# 14audio.net
KiCad netlist of a schematic drawn in Altium Designer
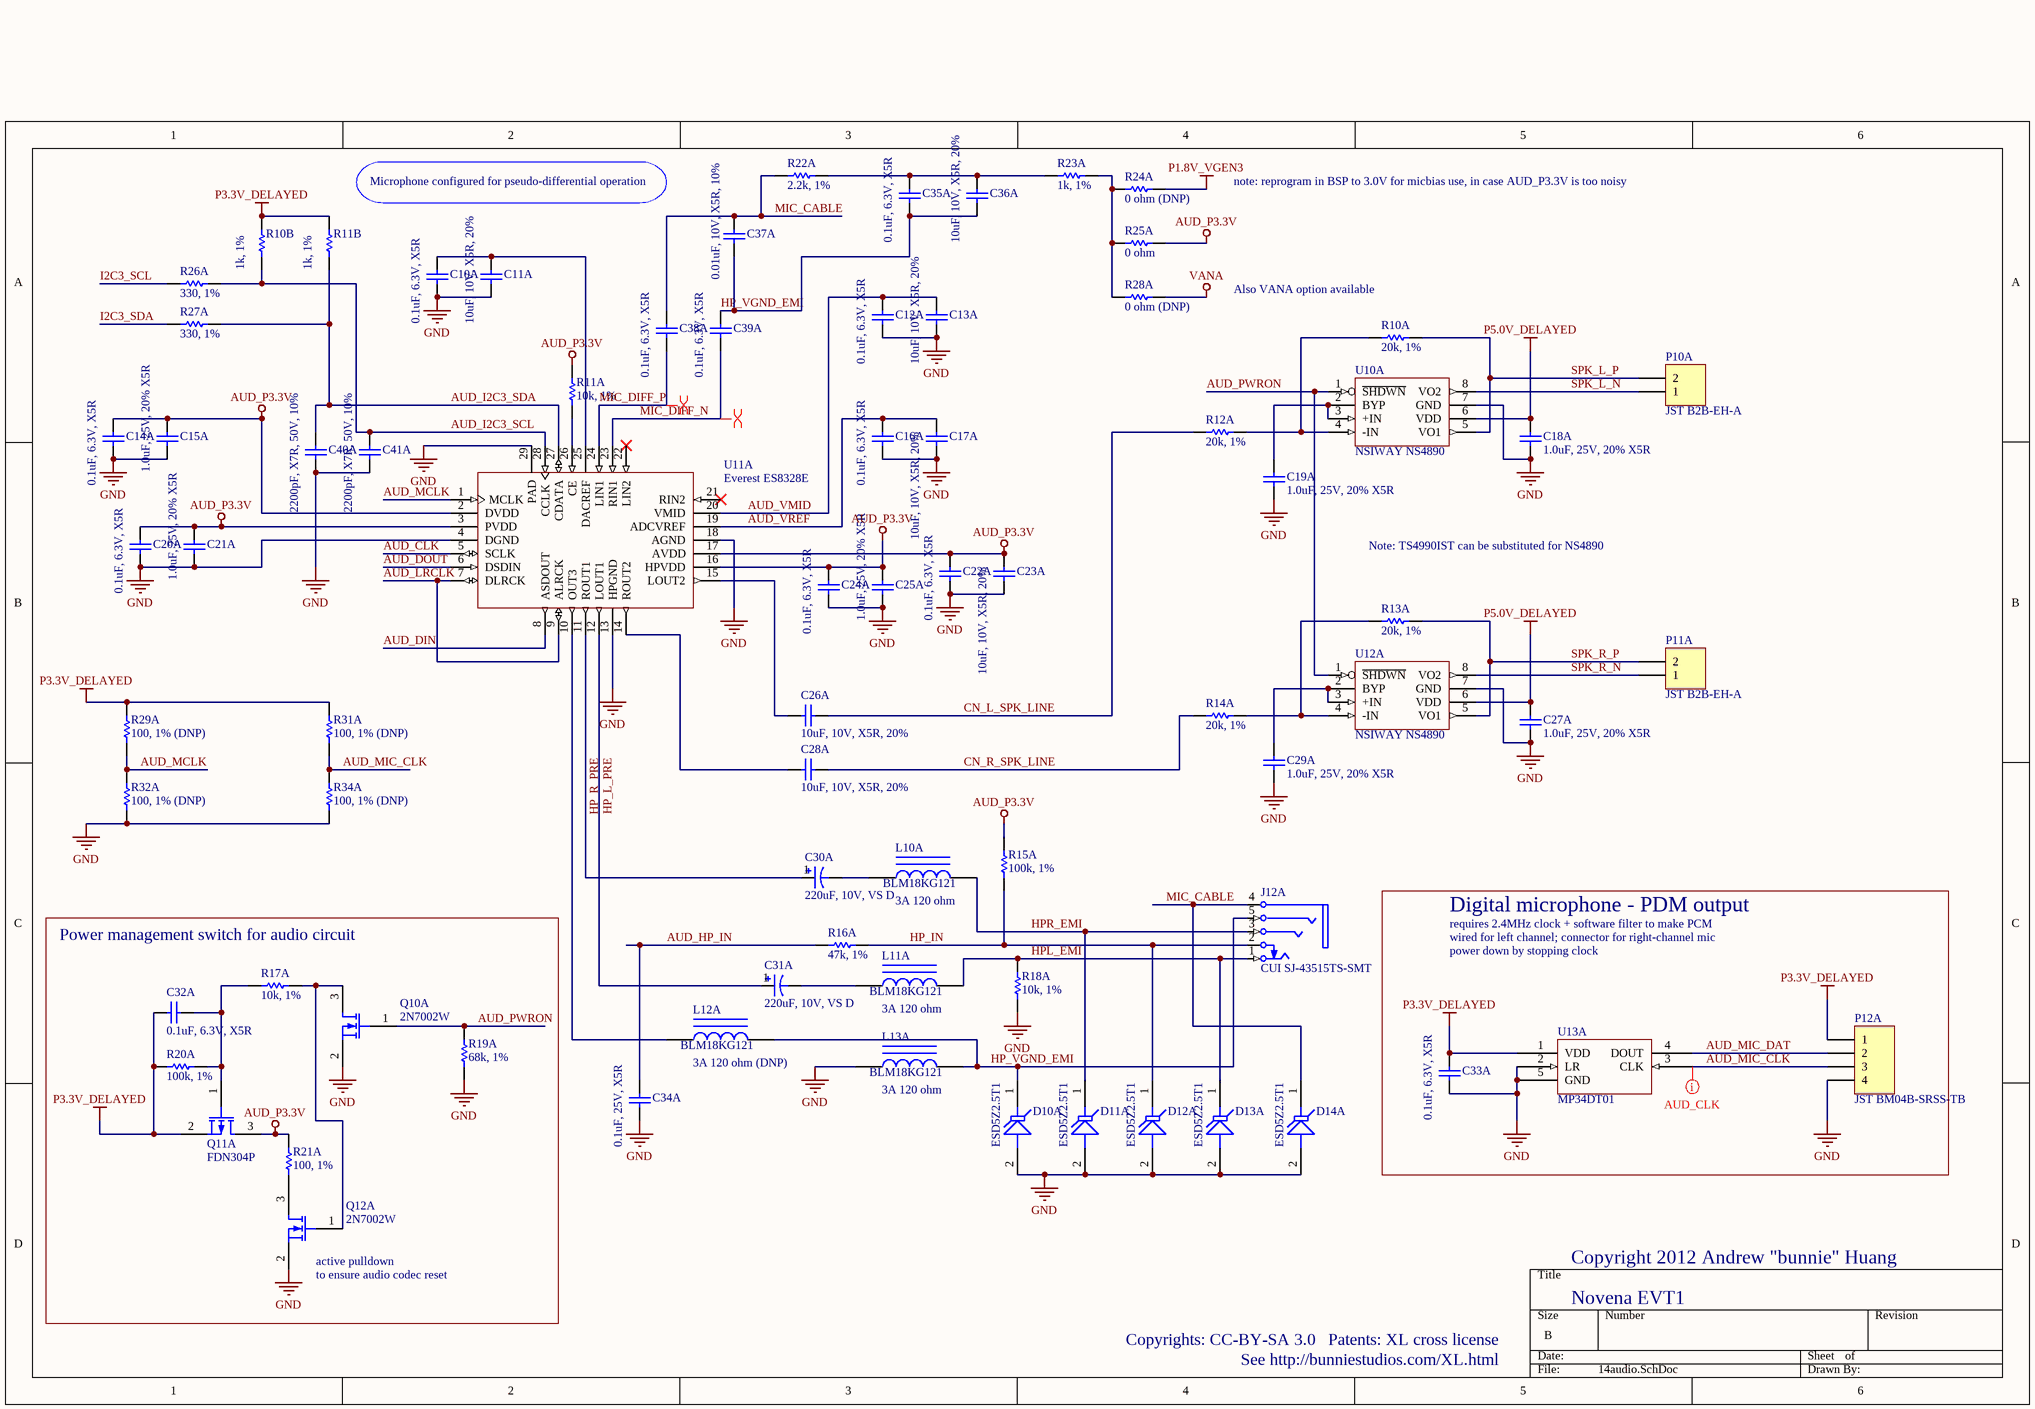
[diagram p0: 14audio.SchDoc]

(export (version "E")
  (design (tool "Eeschema 10.0.6"))
  (components
    (comp (ref "C10A")
      (value "0.1uF, 6.3V, X5R")
      (footprint "CAPC0603N_B")
      (description "Capacitor (Semiconductor SIM Model)")
      (fields (field (name "PUBLISHER") "Altium Limited"))
      (libsource (lib "Miscellaneous Devices") (part "Cap Semi"))
    )
    (comp (ref "C11A")
      (value "10uF, 10V, X5R, 20%")
      (footprint "CAPC1608N")
      (description "Capacitor (Semiconductor SIM Model)")
      (fields (field (name "PUBLISHER") "Altium Limited"))
      (libsource (lib "Miscellaneous Devices") (part "Cap Semi"))
    )
    (comp (ref "C12A")
      (value "0.1uF, 6.3V, X5R")
      (footprint "CAPC0603N_B")
      (description "Capacitor (Semiconductor SIM Model)")
      (fields (field (name "PUBLISHER") "Altium Limited"))
      (libsource (lib "Miscellaneous Devices") (part "Cap Semi"))
    )
    (comp (ref "C13A")
      (value "10uF, 10V, X5R, 20%")
      (footprint "CAPC1608N")
      (description "Capacitor (Semiconductor SIM Model)")
      (fields (field (name "PUBLISHER") "Altium Limited"))
      (libsource (lib "Miscellaneous Devices") (part "Cap Semi"))
    )
    (comp (ref "C14A")
      (value "0.1uF, 6.3V, X5R")
      (footprint "CAPC0603N_B")
      (description "Capacitor (Semiconductor SIM Model)")
      (fields (field (name "PUBLISHER") "Altium Limited"))
      (libsource (lib "Miscellaneous Devices") (part "Cap Semi"))
    )
    (comp (ref "C15A")
      (value "1.0uF, 25V, 20% X5R")
      (footprint "CAPC1608N")
      (description "Capacitor (Semiconductor SIM Model)")
      (fields (field (name "PUBLISHER") "Altium Limited"))
      (libsource (lib "Miscellaneous Devices") (part "Cap Semi"))
    )
    (comp (ref "C16A")
      (value "0.1uF, 6.3V, X5R")
      (footprint "CAPC0603N_B")
      (description "Capacitor (Semiconductor SIM Model)")
      (fields (field (name "PUBLISHER") "Altium Limited"))
      (libsource (lib "Miscellaneous Devices") (part "Cap Semi"))
    )
    (comp (ref "C17A")
      (value "10uF, 10V, X5R, 20%")
      (footprint "CAPC1608N")
      (description "Capacitor (Semiconductor SIM Model)")
      (fields (field (name "PUBLISHER") "Altium Limited"))
      (libsource (lib "Miscellaneous Devices") (part "Cap Semi"))
    )
    (comp (ref "C18A")
      (value "1.0uF, 25V, 20% X5R")
      (footprint "CAPC1608N")
      (description "Capacitor (Semiconductor SIM Model)")
      (fields (field (name "PUBLISHER") "Altium Limited"))
      (libsource (lib "Miscellaneous Devices") (part "Cap Semi"))
    )
    (comp (ref "C19A")
      (value "1.0uF, 25V, 20% X5R")
      (footprint "CAPC1608N")
      (description "Capacitor (Semiconductor SIM Model)")
      (fields (field (name "PUBLISHER") "Altium Limited"))
      (libsource (lib "Miscellaneous Devices") (part "Cap Semi"))
    )
    (comp (ref "C20A")
      (value "0.1uF, 6.3V, X5R")
      (footprint "CAPC0603N_B")
      (description "Capacitor (Semiconductor SIM Model)")
      (fields (field (name "PUBLISHER") "Altium Limited"))
      (libsource (lib "Miscellaneous Devices") (part "Cap Semi"))
    )
    (comp (ref "C21A")
      (value "1.0uF, 25V, 20% X5R")
      (footprint "CAPC1608N")
      (description "Capacitor (Semiconductor SIM Model)")
      (fields (field (name "PUBLISHER") "Altium Limited"))
      (libsource (lib "Miscellaneous Devices") (part "Cap Semi"))
    )
    (comp (ref "C22A")
      (value "0.1uF, 6.3V, X5R")
      (footprint "CAPC0603N_B")
      (description "Capacitor (Semiconductor SIM Model)")
      (fields (field (name "PUBLISHER") "Altium Limited"))
      (libsource (lib "Miscellaneous Devices") (part "Cap Semi"))
    )
    (comp (ref "C23A")
      (value "10uF, 10V, X5R, 20%")
      (footprint "CAPC1608N")
      (description "Capacitor (Semiconductor SIM Model)")
      (fields (field (name "PUBLISHER") "Altium Limited"))
      (libsource (lib "Miscellaneous Devices") (part "Cap Semi"))
    )
    (comp (ref "C24A")
      (value "0.1uF, 6.3V, X5R")
      (footprint "CAPC0603N_B")
      (description "Capacitor (Semiconductor SIM Model)")
      (fields (field (name "PUBLISHER") "Altium Limited"))
      (libsource (lib "Miscellaneous Devices") (part "Cap Semi"))
    )
    (comp (ref "C25A")
      (value "1.0uF, 25V, 20% X5R")
      (footprint "CAPC1608N")
      (description "Capacitor (Semiconductor SIM Model)")
      (fields (field (name "PUBLISHER") "Altium Limited"))
      (libsource (lib "Miscellaneous Devices") (part "Cap Semi"))
    )
    (comp (ref "C26A")
      (value "10uF, 10V, X5R, 20%")
      (footprint "CAPC1608N")
      (description "Capacitor (Semiconductor SIM Model)")
      (fields (field (name "PUBLISHER") "Altium Limited"))
      (libsource (lib "Miscellaneous Devices") (part "Cap Semi"))
    )
    (comp (ref "C27A")
      (value "1.0uF, 25V, 20% X5R")
      (footprint "CAPC1608N")
      (description "Capacitor (Semiconductor SIM Model)")
      (fields (field (name "PUBLISHER") "Altium Limited"))
      (libsource (lib "Miscellaneous Devices") (part "Cap Semi"))
    )
    (comp (ref "C28A")
      (value "10uF, 10V, X5R, 20%")
      (footprint "CAPC1608N")
      (description "Capacitor (Semiconductor SIM Model)")
      (fields (field (name "PUBLISHER") "Altium Limited"))
      (libsource (lib "Miscellaneous Devices") (part "Cap Semi"))
    )
    (comp (ref "C29A")
      (value "1.0uF, 25V, 20% X5R")
      (footprint "CAPC1608N")
      (description "Capacitor (Semiconductor SIM Model)")
      (fields (field (name "PUBLISHER") "Altium Limited"))
      (libsource (lib "Miscellaneous Devices") (part "Cap Semi"))
    )
    (comp (ref "C30A")
      (value "220uF, 10V, VS D")
      (footprint "6004pcb:ALCAP_D")
      (description "Polarized Capacitor (Surface Mount)")
      (fields (field (name "PUBLISHER") "Altium Limited"))
      (libsource (lib "Miscellaneous Devices") (part "Cap Pol3"))
    )
    (comp (ref "C31A")
      (value "220uF, 10V, VS D")
      (footprint "6004pcb:ALCAP_D")
      (description "Polarized Capacitor (Surface Mount)")
      (fields (field (name "PUBLISHER") "Altium Limited"))
      (libsource (lib "Miscellaneous Devices") (part "Cap Pol3"))
    )
    (comp (ref "C32A")
      (value "0.1uF, 6.3V, X5R")
      (footprint "CAPC0603N_B")
      (description "Capacitor (Semiconductor SIM Model)")
      (fields (field (name "PUBLISHER") "Altium Limited"))
      (libsource (lib "Miscellaneous Devices") (part "Cap Semi"))
    )
    (comp (ref "C33A")
      (value "0.1uF, 6.3V, X5R")
      (footprint "CAPC0603N_B")
      (description "Capacitor (Semiconductor SIM Model)")
      (fields (field (name "PUBLISHER") "Altium Limited"))
      (libsource (lib "Miscellaneous Devices") (part "Cap Semi"))
    )
    (comp (ref "C34A")
      (value "0.1uF, 25V, X5R")
      (footprint "CAPC1005N")
      (description "Capacitor (Semiconductor SIM Model)")
      (fields (field (name "PUBLISHER") "Altium Limited"))
      (libsource (lib "Miscellaneous Devices") (part "Cap Semi"))
    )
    (comp (ref "C35A")
      (value "0.1uF, 6.3V, X5R")
      (footprint "CAPC0603N_B")
      (description "Capacitor (Semiconductor SIM Model)")
      (fields (field (name "PUBLISHER") "Altium Limited"))
      (libsource (lib "Miscellaneous Devices") (part "Cap Semi"))
    )
    (comp (ref "C36A")
      (value "10uF, 10V, X5R, 20%")
      (footprint "CAPC1608N")
      (description "Capacitor (Semiconductor SIM Model)")
      (fields (field (name "PUBLISHER") "Altium Limited"))
      (libsource (lib "Miscellaneous Devices") (part "Cap Semi"))
    )
    (comp (ref "C37A")
      (value "0.01uF, 10V, X5R, 10%")
      (footprint "CAPC0603N_B")
      (description "Capacitor (Semiconductor SIM Model)")
      (fields (field (name "PUBLISHER") "Altium Limited"))
      (libsource (lib "Miscellaneous Devices") (part "Cap Semi"))
    )
    (comp (ref "C38A")
      (value "0.1uF, 6.3V, X5R")
      (footprint "CAPC0603N_B")
      (description "Capacitor (Semiconductor SIM Model)")
      (fields (field (name "PUBLISHER") "Altium Limited"))
      (libsource (lib "Miscellaneous Devices") (part "Cap Semi"))
    )
    (comp (ref "C39A")
      (value "0.1uF, 6.3V, X5R")
      (footprint "CAPC0603N_B")
      (description "Capacitor (Semiconductor SIM Model)")
      (fields (field (name "PUBLISHER") "Altium Limited"))
      (libsource (lib "Miscellaneous Devices") (part "Cap Semi"))
    )
    (comp (ref "C40A")
      (value "2200pF, X7R, 50V, 10%")
      (footprint "CAPC1005N")
      (description "Capacitor (Semiconductor SIM Model)")
      (fields (field (name "PUBLISHER") "Altium Limited"))
      (libsource (lib "Miscellaneous Devices") (part "Cap Semi"))
    )
    (comp (ref "C41A")
      (value "2200pF, X7R, 50V, 10%")
      (footprint "CAPC1005N")
      (description "Capacitor (Semiconductor SIM Model)")
      (fields (field (name "PUBLISHER") "Altium Limited"))
      (libsource (lib "Miscellaneous Devices") (part "Cap Semi"))
    )
    (comp (ref "D10A")
      (value "ESD5Z2.5T1")
      (footprint "SOD-523")
      (description "On Semi 3.3V standoff TVS diode")
      (fields (field (name "PUBLISHER") "Altium Limited"))
      (libsource (lib "Miscellaneous Devices") (part "Tranzorb"))
    )
    (comp (ref "D11A")
      (value "ESD5Z2.5T1")
      (footprint "SOD-523")
      (description "On Semi 3.3V standoff TVS diode")
      (fields (field (name "PUBLISHER") "Altium Limited"))
      (libsource (lib "Miscellaneous Devices") (part "Tranzorb"))
    )
    (comp (ref "D12A")
      (value "ESD5Z2.5T1")
      (footprint "SOD-523")
      (description "On Semi 3.3V standoff TVS diode")
      (fields (field (name "PUBLISHER") "Altium Limited"))
      (libsource (lib "Miscellaneous Devices") (part "Tranzorb"))
    )
    (comp (ref "D13A")
      (value "ESD5Z2.5T1")
      (footprint "SOD-523")
      (description "On Semi 3.3V standoff TVS diode")
      (fields (field (name "PUBLISHER") "Altium Limited"))
      (libsource (lib "Miscellaneous Devices") (part "Tranzorb"))
    )
    (comp (ref "D14A")
      (value "ESD5Z2.5T1")
      (footprint "SOD-523")
      (description "On Semi 3.3V standoff TVS diode")
      (fields (field (name "PUBLISHER") "Altium Limited"))
      (libsource (lib "Miscellaneous Devices") (part "Tranzorb"))
    )
    (comp (ref "J12A")
      (value "CUI SJ-43515TS-SMT")
      (footprint "CUI_SJ_43515TS-SMT")
      (description "Jack Socket, 3.5mm, SMT, 4-conductor")
      (fields (field (name "PUBLISHER") "Altium Limited"))
      (libsource (lib "commonsch") (part "Phonejack4 TN"))
    )
    (comp (ref "L10A")
      (value "BLM18KG121")
      (footprint "INDC1608AN")
      (description "Magnetic-Core Inductor")
      (fields (field (name "ALTIUM_VALUE") "3A 120 ohm") (field (name "PUBLISHER") "Altium Limited"))
      (libsource (lib "Miscellaneous Devices") (part "Inductor Iron"))
    )
    (comp (ref "L11A")
      (value "BLM18KG121")
      (footprint "INDC1608AN")
      (description "Magnetic-Core Inductor")
      (fields (field (name "ALTIUM_VALUE") "3A 120 ohm") (field (name "PUBLISHER") "Altium Limited"))
      (libsource (lib "Miscellaneous Devices") (part "Inductor Iron"))
    )
    (comp (ref "L12A")
      (value "BLM18KG121")
      (footprint "INDC1608AN")
      (description "Magnetic-Core Inductor")
      (fields (field (name "ALTIUM_VALUE") "3A 120 ohm (DNP)") (field (name "PUBLISHER") "Altium Limited"))
      (libsource (lib "Miscellaneous Devices") (part "Inductor Iron"))
    )
    (comp (ref "L13A")
      (value "BLM18KG121")
      (footprint "INDC1608AN")
      (description "Magnetic-Core Inductor")
      (fields (field (name "ALTIUM_VALUE") "3A 120 ohm") (field (name "PUBLISHER") "Altium Limited"))
      (libsource (lib "Miscellaneous Devices") (part "Inductor Iron"))
    )
    (comp (ref "P10A")
      (value "JST B2B-EH-A")
      (footprint "JST_B2B_EH_A")
      (description "Header, 2-Pin")
      (fields (field (name "PUBLISHER") "Altium Limited"))
      (libsource (lib "Miscellaneous Connectors") (part "Header 2"))
    )
    (comp (ref "P11A")
      (value "JST B2B-EH-A")
      (footprint "JST_B2B_EH_A")
      (description "Header, 2-Pin")
      (fields (field (name "PUBLISHER") "Altium Limited"))
      (libsource (lib "Miscellaneous Connectors") (part "Header 2"))
    )
    (comp (ref "P12A")
      (value "JST BM04B-SRSS-TB")
      (footprint "JST_BM04B_SRSS_TB")
      (description "Header, 4-Pin, Right Angle")
      (fields (field (name "PUBLISHER") "Altium Limited"))
      (libsource (lib "Miscellaneous Connectors") (part "Header 4H"))
    )
    (comp (ref "Q10A")
      (value "2N7002W")
      (footprint "SOT323-3AN")
      (description "N-Channel MOSFET")
      (fields (field (name "PUBLISHER") "Altium Limited"))
      (libsource (lib "Miscellaneous Devices") (part "MOSFET-N"))
    )
    (comp (ref "Q11A")
      (value "FDN304P")
      (footprint "SOT23-3N")
      (description "P-Channel MOSFET")
      (fields (field (name "PUBLISHER") "Altium Limited"))
      (libsource (lib "Miscellaneous Devices") (part "MOSFET-P"))
    )
    (comp (ref "Q12A")
      (value "2N7002W")
      (footprint "SOT323-3AN")
      (description "N-Channel MOSFET")
      (fields (field (name "PUBLISHER") "Altium Limited"))
      (libsource (lib "Miscellaneous Devices") (part "MOSFET-N"))
    )
    (comp (ref "R10A")
      (value "20k, 1%")
      (footprint "RESC1005N")
      (description "Resistor")
      (fields (field (name "PUBLISHER") "Altium Limited"))
      (libsource (lib "Miscellaneous Devices") (part "Res1"))
    )
    (comp (ref "R10B")
      (value "1k, 1%")
      (footprint "RESC1005N")
      (description "Resistor")
      (fields (field (name "PUBLISHER") "Altium Limited"))
      (libsource (lib "Miscellaneous Devices") (part "Res1"))
    )
    (comp (ref "R11A")
      (value "10k, 1%")
      (footprint "RESC1005N")
      (description "Resistor")
      (fields (field (name "PUBLISHER") "Altium Limited"))
      (libsource (lib "Miscellaneous Devices") (part "Res1"))
    )
    (comp (ref "R11B")
      (value "1k, 1%")
      (footprint "RESC1005N")
      (description "Resistor")
      (fields (field (name "PUBLISHER") "Altium Limited"))
      (libsource (lib "Miscellaneous Devices") (part "Res1"))
    )
    (comp (ref "R12A")
      (value "20k, 1%")
      (footprint "RESC1005N")
      (description "Resistor")
      (fields (field (name "PUBLISHER") "Altium Limited"))
      (libsource (lib "Miscellaneous Devices") (part "Res1"))
    )
    (comp (ref "R13A")
      (value "20k, 1%")
      (footprint "RESC1005N")
      (description "Resistor")
      (fields (field (name "PUBLISHER") "Altium Limited"))
      (libsource (lib "Miscellaneous Devices") (part "Res1"))
    )
    (comp (ref "R14A")
      (value "20k, 1%")
      (footprint "RESC1005N")
      (description "Resistor")
      (fields (field (name "PUBLISHER") "Altium Limited"))
      (libsource (lib "Miscellaneous Devices") (part "Res1"))
    )
    (comp (ref "R15A")
      (value "100k, 1%")
      (footprint "RESC1005N")
      (description "Resistor")
      (fields (field (name "PUBLISHER") "Altium Limited"))
      (libsource (lib "Miscellaneous Devices") (part "Res1"))
    )
    (comp (ref "R16A")
      (value "47k, 1%")
      (footprint "RESC1005N")
      (description "Resistor")
      (fields (field (name "PUBLISHER") "Altium Limited"))
      (libsource (lib "Miscellaneous Devices") (part "Res1"))
    )
    (comp (ref "R17A")
      (value "10k, 1%")
      (footprint "RESC1005N")
      (description "Resistor")
      (fields (field (name "PUBLISHER") "Altium Limited"))
      (libsource (lib "Miscellaneous Devices") (part "Res1"))
    )
    (comp (ref "R18A")
      (value "10k, 1%")
      (footprint "RESC1005N")
      (description "Resistor")
      (fields (field (name "PUBLISHER") "Altium Limited"))
      (libsource (lib "Miscellaneous Devices") (part "Res1"))
    )
    (comp (ref "R19A")
      (value "68k, 1%")
      (footprint "RESC1005N")
      (description "Resistor")
      (fields (field (name "PUBLISHER") "Altium Limited"))
      (libsource (lib "Miscellaneous Devices") (part "Res1"))
    )
    (comp (ref "R20A")
      (value "100k, 1%")
      (footprint "RESC1005N")
      (description "Resistor")
      (fields (field (name "PUBLISHER") "Altium Limited"))
      (libsource (lib "Miscellaneous Devices") (part "Res1"))
    )
    (comp (ref "R21A")
      (value "100, 1%")
      (footprint "RESC1005N")
      (description "Resistor")
      (fields (field (name "PUBLISHER") "Altium Limited"))
      (libsource (lib "Miscellaneous Devices") (part "Res1"))
    )
    (comp (ref "R22A")
      (value "2.2k, 1%")
      (footprint "RESC1005N")
      (description "Resistor")
      (fields (field (name "PUBLISHER") "Altium Limited"))
      (libsource (lib "Miscellaneous Devices") (part "Res1"))
    )
    (comp (ref "R23A")
      (value "1k, 1%")
      (footprint "RESC1005N")
      (description "Resistor")
      (fields (field (name "PUBLISHER") "Altium Limited"))
      (libsource (lib "Miscellaneous Devices") (part "Res1"))
    )
    (comp (ref "R24A")
      (value "0 ohm (DNP)")
      (footprint "RESC1005N")
      (description "Resistor")
      (fields (field (name "PUBLISHER") "Altium Limited"))
      (libsource (lib "Miscellaneous Devices") (part "Res1"))
    )
    (comp (ref "R25A")
      (value "0 ohm")
      (footprint "RESC1005N")
      (description "Resistor")
      (fields (field (name "PUBLISHER") "Altium Limited"))
      (libsource (lib "Miscellaneous Devices") (part "Res1"))
    )
    (comp (ref "R26A")
      (value "330, 1%")
      (footprint "RESC1005N")
      (description "Resistor")
      (fields (field (name "PUBLISHER") "Altium Limited"))
      (libsource (lib "Miscellaneous Devices") (part "Res1"))
    )
    (comp (ref "R27A")
      (value "330, 1%")
      (footprint "RESC1005N")
      (description "Resistor")
      (fields (field (name "PUBLISHER") "Altium Limited"))
      (libsource (lib "Miscellaneous Devices") (part "Res1"))
    )
    (comp (ref "R28A")
      (value "0 ohm (DNP)")
      (footprint "RESC1005N")
      (description "Resistor")
      (fields (field (name "PUBLISHER") "Altium Limited"))
      (libsource (lib "Miscellaneous Devices") (part "Res1"))
    )
    (comp (ref "R29A")
      (value "100, 1% (DNP)")
      (footprint "RESC1005N")
      (description "Resistor")
      (fields (field (name "PUBLISHER") "Altium Limited"))
      (libsource (lib "Miscellaneous Devices") (part "Res1"))
    )
    (comp (ref "R31A")
      (value "100, 1% (DNP)")
      (footprint "RESC1005N")
      (description "Resistor")
      (fields (field (name "PUBLISHER") "Altium Limited"))
      (libsource (lib "Miscellaneous Devices") (part "Res1"))
    )
    (comp (ref "R32A")
      (value "100, 1% (DNP)")
      (footprint "RESC1005N")
      (description "Resistor")
      (fields (field (name "PUBLISHER") "Altium Limited"))
      (libsource (lib "Miscellaneous Devices") (part "Res1"))
    )
    (comp (ref "R34A")
      (value "100, 1% (DNP)")
      (footprint "RESC1005N")
      (description "Resistor")
      (fields (field (name "PUBLISHER") "Altium Limited"))
      (libsource (lib "Miscellaneous Devices") (part "Res1"))
    )
    (comp (ref "U10A")
      (value "NSIWAY NS4890")
      (footprint "MSOP8")
      (description "1W 8 ohm low-cost amplifier")
      (libsource (lib "commonsch") (part "NSIWAY_NS4890"))
    )
    (comp (ref "U11A")
      (value "Everest ES8328E")
      (footprint "QFN50P500X500-28V1N")
      (description "Low-cost audio CODEC by Everest")
      (libsource (lib "commonsch") (part "Everest_ES8328"))
    )
    (comp (ref "U12A")
      (value "NSIWAY NS4890")
      (footprint "MSOP8")
      (description "1W 8 ohm low-cost amplifier")
      (libsource (lib "commonsch") (part "NSIWAY_NS4890"))
    )
    (comp (ref "U13A")
      (value "MP34DT01")
      (footprint "STM_HCLGA_3MMx4MMx1MM")
      (description "ST Micro silicon microphone, PDM digital output")
      (libsource (lib "commonsch") (part "MP34DT01"))
    )
  )
  (nets
    (net (code "1") (name "/AUD_CLK") (class "Default")
      (node (ref "U11A") (pin "5") (pinfunction "SCLK_5") (pintype "bidirectional"))
    )
    (net (code "2") (name "/AUD_DIN") (class "Default")
      (node (ref "U11A") (pin "8") (pinfunction "ASDOUT_8") (pintype "output"))
    )
    (net (code "3") (name "/AUD_DOUT") (class "Default")
      (node (ref "U11A") (pin "6") (pinfunction "DSDIN_6") (pintype "input"))
    )
    (net (code "4") (name "/AUD_HP_IN") (class "Default")
      (node (ref "C34A") (pin "2") (pinfunction "2_2") (pintype "passive"))
      (node (ref "R16A") (pin "2") (pinfunction "2_2") (pintype "passive"))
    )
    (net (code "5") (name "/AUD_I2C3_SCL") (class "Default")
      (node (ref "C41A") (pin "2") (pinfunction "2_2") (pintype "passive"))
      (node (ref "R10B") (pin "1") (pinfunction "1_1") (pintype "passive"))
      (node (ref "R26A") (pin "1") (pinfunction "1_1") (pintype "passive"))
      (node (ref "U11A") (pin "28") (pinfunction "CCLK_28") (pintype "input"))
    )
    (net (code "6") (name "/AUD_I2C3_SDA") (class "Default")
      (node (ref "C40A") (pin "2") (pinfunction "2_2") (pintype "passive"))
      (node (ref "R11B") (pin "1") (pinfunction "1_1") (pintype "passive"))
      (node (ref "R27A") (pin "1") (pinfunction "1_1") (pintype "passive"))
      (node (ref "U11A") (pin "27") (pinfunction "CDATA_27") (pintype "bidirectional"))
    )
    (net (code "7") (name "/AUD_LRCLK") (class "Default")
      (node (ref "U11A") (pin "7") (pinfunction "DLRCK_7") (pintype "bidirectional"))
      (node (ref "U11A") (pin "9") (pinfunction "ALRCK_9") (pintype "bidirectional"))
    )
    (net (code "8") (name "/AUD_MCLK") (class "Default")
      (node (ref "R29A") (pin "1") (pinfunction "1_1") (pintype "passive"))
      (node (ref "R32A") (pin "2") (pinfunction "2_2") (pintype "passive"))
      (node (ref "U11A") (pin "1") (pinfunction "MCLK_1") (pintype "input"))
    )
    (net (code "9") (name "/AUD_MIC_CLK") (class "Default")
      (node (ref "P12A") (pin "3") (pinfunction "3_3") (pintype "passive"))
      (node (ref "R31A") (pin "1") (pinfunction "1_1") (pintype "passive"))
      (node (ref "R34A") (pin "2") (pinfunction "2_2") (pintype "passive"))
      (node (ref "U13A") (pin "3") (pinfunction "CLK_3") (pintype "input"))
    )
    (net (code "10") (name "/AUD_MIC_DAT") (class "Default")
      (node (ref "P12A") (pin "2") (pinfunction "2_2") (pintype "passive"))
      (node (ref "U13A") (pin "4") (pinfunction "DOUT_4") (pintype "tri_state"))
    )
    (net (code "11") (name "/AUD_PWRON") (class "Default")
      (node (ref "Q10A") (pin "1") (pinfunction "G_1") (pintype "passive"))
      (node (ref "R19A") (pin "1") (pinfunction "1_1") (pintype "passive"))
      (node (ref "U10A") (pin "1") (pinfunction "~{SHDWN}_1") (pintype "input"))
      (node (ref "U12A") (pin "1") (pinfunction "~{SHDWN}_1") (pintype "input"))
    )
    (net (code "12") (name "/AUD_VMID") (class "Default")
      (node (ref "C12A") (pin "2") (pinfunction "2_2") (pintype "passive"))
      (node (ref "C13A") (pin "1") (pinfunction "1_1") (pintype "passive"))
      (node (ref "U11A") (pin "20") (pinfunction "VMID_20") (pintype "passive"))
    )
    (net (code "13") (name "/AUD_VREF") (class "Default")
      (node (ref "C16A") (pin "2") (pinfunction "2_2") (pintype "passive"))
      (node (ref "C17A") (pin "1") (pinfunction "1_1") (pintype "passive"))
      (node (ref "U11A") (pin "19") (pinfunction "ADCVREF_19") (pintype "passive"))
    )
    (net (code "14") (name "/CN_L_SPK_LINE") (class "Default")
      (node (ref "C26A") (pin "2") (pinfunction "2_2") (pintype "passive"))
      (node (ref "R12A") (pin "2") (pinfunction "2_2") (pintype "passive"))
    )
    (net (code "15") (name "/CN_R_SPK_LINE") (class "Default")
      (node (ref "C28A") (pin "2") (pinfunction "2_2") (pintype "passive"))
      (node (ref "R14A") (pin "2") (pinfunction "2_2") (pintype "passive"))
    )
    (net (code "16") (name "/HPL_EMI") (class "Default")
      (node (ref "D13A") (pin "1") (pinfunction "K_1") (pintype "passive"))
      (node (ref "J12A") (pin "1") (pinfunction "T_1") (pintype "input"))
      (node (ref "L11A") (pin "2") (pinfunction "2_2") (pintype "passive"))
      (node (ref "R18A") (pin "1") (pinfunction "1_1") (pintype "passive"))
    )
    (net (code "17") (name "/HPR_EMI") (class "Default")
      (node (ref "D11A") (pin "1") (pinfunction "K_1") (pintype "passive"))
      (node (ref "J12A") (pin "3") (pinfunction "R_3") (pintype "input"))
      (node (ref "L10A") (pin "2") (pinfunction "2_2") (pintype "passive"))
    )
    (net (code "18") (name "/HP_IN") (class "Default")
      (node (ref "D12A") (pin "1") (pinfunction "K_1") (pintype "passive"))
      (node (ref "J12A") (pin "2") (pinfunction "TN_2") (pintype "passive"))
      (node (ref "R15A") (pin "1") (pinfunction "1_1") (pintype "passive"))
      (node (ref "R16A") (pin "1") (pinfunction "1_1") (pintype "passive"))
    )
    (net (code "19") (name "/HP_L_PRE") (class "Default")
      (node (ref "C31A") (pin "1") (pinfunction "1_1") (pintype "passive"))
      (node (ref "U11A") (pin "12") (pinfunction "LOUT1_12") (pintype "output"))
    )
    (net (code "20") (name "/HP_R_PRE") (class "Default")
      (node (ref "C30A") (pin "1") (pinfunction "1_1") (pintype "passive"))
      (node (ref "U11A") (pin "11") (pinfunction "ROUT1_11") (pintype "output"))
    )
    (net (code "21") (name "/HP_VGND_EMI") (class "Default")
      (node (ref "C35A") (pin "1") (pinfunction "1_1") (pintype "passive"))
      (node (ref "C36A") (pin "2") (pinfunction "2_2") (pintype "passive"))
      (node (ref "C37A") (pin "2") (pinfunction "2_2") (pintype "passive"))
      (node (ref "C39A") (pin "2") (pinfunction "2_2") (pintype "passive"))
      (node (ref "D10A") (pin "1") (pinfunction "K_1") (pintype "passive"))
      (node (ref "J12A") (pin "5") (pinfunction "R_5") (pintype "input"))
      (node (ref "L12A") (pin "2") (pinfunction "2_2") (pintype "passive"))
      (node (ref "L13A") (pin "2") (pinfunction "2_2") (pintype "passive"))
    )
    (net (code "22") (name "/I2C3_SCL") (class "Default")
      (node (ref "R26A") (pin "2") (pinfunction "2_2") (pintype "passive"))
    )
    (net (code "23") (name "/I2C3_SDA") (class "Default")
      (node (ref "R27A") (pin "2") (pinfunction "2_2") (pintype "passive"))
    )
    (net (code "24") (name "/MIC_CABLE") (class "Default")
      (node (ref "C37A") (pin "1") (pinfunction "1_1") (pintype "passive"))
      (node (ref "C38A") (pin "2") (pinfunction "2_2") (pintype "passive"))
      (node (ref "D14A") (pin "1") (pinfunction "K_1") (pintype "passive"))
      (node (ref "J12A") (pin "4") (pinfunction "S_4") (pintype "power_in"))
      (node (ref "R22A") (pin "1") (pinfunction "1_1") (pintype "passive"))
    )
    (net (code "25") (name "/MIC_DIFF_N") (class "Default")
      (node (ref "C39A") (pin "1") (pinfunction "1_1") (pintype "passive"))
      (node (ref "U11A") (pin "23") (pinfunction "RIN1_23") (pintype "input"))
    )
    (net (code "26") (name "/MIC_DIFF_P") (class "Default")
      (node (ref "C38A") (pin "1") (pinfunction "1_1") (pintype "passive"))
      (node (ref "U11A") (pin "24") (pinfunction "LIN1_24") (pintype "input"))
    )
    (net (code "27") (name "/SPK_L_N") (class "Default")
      (node (ref "P10A") (pin "1") (pinfunction "1_1") (pintype "passive"))
      (node (ref "U10A") (pin "8") (pinfunction "VO2_8") (pintype "output"))
    )
    (net (code "28") (name "/SPK_L_P") (class "Default")
      (node (ref "P10A") (pin "2") (pinfunction "2_2") (pintype "passive"))
      (node (ref "R10A") (pin "1") (pinfunction "1_1") (pintype "passive"))
      (node (ref "U10A") (pin "5") (pinfunction "VO1_5") (pintype "output"))
    )
    (net (code "29") (name "/SPK_R_N") (class "Default")
      (node (ref "P11A") (pin "1") (pinfunction "1_1") (pintype "passive"))
      (node (ref "U12A") (pin "8") (pinfunction "VO2_8") (pintype "output"))
    )
    (net (code "30") (name "/SPK_R_P") (class "Default")
      (node (ref "P11A") (pin "2") (pinfunction "2_2") (pintype "passive"))
      (node (ref "R13A") (pin "1") (pinfunction "1_1") (pintype "passive"))
      (node (ref "U12A") (pin "5") (pinfunction "VO1_5") (pintype "output"))
    )
    (net (code "31") (name "AUD_P3.3V") (class "Default")
      (node (ref "C14A") (pin "2") (pinfunction "2_2") (pintype "passive"))
      (node (ref "C15A") (pin "2") (pinfunction "2_2") (pintype "passive"))
      (node (ref "C20A") (pin "2") (pinfunction "2_2") (pintype "passive"))
      (node (ref "C21A") (pin "2") (pinfunction "2_2") (pintype "passive"))
      (node (ref "C22A") (pin "2") (pinfunction "2_2") (pintype "passive"))
      (node (ref "C23A") (pin "1") (pinfunction "1_1") (pintype "passive"))
      (node (ref "C24A") (pin "2") (pinfunction "2_2") (pintype "passive"))
      (node (ref "C25A") (pin "2") (pinfunction "2_2") (pintype "passive"))
      (node (ref "Q11A") (pin "3") (pinfunction "D_3") (pintype "passive"))
      (node (ref "R11A") (pin "2") (pinfunction "2_2") (pintype "passive"))
      (node (ref "R15A") (pin "2") (pinfunction "2_2") (pintype "passive"))
      (node (ref "R21A") (pin "1") (pinfunction "1_1") (pintype "passive"))
      (node (ref "R25A") (pin "2") (pinfunction "2_2") (pintype "passive"))
      (node (ref "U11A") (pin "16") (pinfunction "HPVDD_16") (pintype "power_in"))
      (node (ref "U11A") (pin "17") (pinfunction "AVDD_17") (pintype "power_in"))
      (node (ref "U11A") (pin "2") (pinfunction "DVDD_2") (pintype "power_in"))
      (node (ref "U11A") (pin "3") (pinfunction "PVDD_3") (pintype "power_in"))
    )
    (net (code "32") (name "GND") (class "Default")
      (node (ref "C10A") (pin "1") (pinfunction "1_1") (pintype "passive"))
      (node (ref "C11A") (pin "2") (pinfunction "2_2") (pintype "passive"))
      (node (ref "C12A") (pin "1") (pinfunction "1_1") (pintype "passive"))
      (node (ref "C13A") (pin "2") (pinfunction "2_2") (pintype "passive"))
      (node (ref "C14A") (pin "1") (pinfunction "1_1") (pintype "passive"))
      (node (ref "C15A") (pin "1") (pinfunction "1_1") (pintype "passive"))
      (node (ref "C16A") (pin "1") (pinfunction "1_1") (pintype "passive"))
      (node (ref "C17A") (pin "2") (pinfunction "2_2") (pintype "passive"))
      (node (ref "C18A") (pin "1") (pinfunction "1_1") (pintype "passive"))
      (node (ref "C19A") (pin "1") (pinfunction "1_1") (pintype "passive"))
      (node (ref "C20A") (pin "1") (pinfunction "1_1") (pintype "passive"))
      (node (ref "C21A") (pin "1") (pinfunction "1_1") (pintype "passive"))
      (node (ref "C22A") (pin "1") (pinfunction "1_1") (pintype "passive"))
      (node (ref "C23A") (pin "2") (pinfunction "2_2") (pintype "passive"))
      (node (ref "C24A") (pin "1") (pinfunction "1_1") (pintype "passive"))
      (node (ref "C25A") (pin "1") (pinfunction "1_1") (pintype "passive"))
      (node (ref "C27A") (pin "1") (pinfunction "1_1") (pintype "passive"))
      (node (ref "C29A") (pin "1") (pinfunction "1_1") (pintype "passive"))
      (node (ref "C33A") (pin "1") (pinfunction "1_1") (pintype "passive"))
      (node (ref "C34A") (pin "1") (pinfunction "1_1") (pintype "passive"))
      (node (ref "C40A") (pin "1") (pinfunction "1_1") (pintype "passive"))
      (node (ref "C41A") (pin "1") (pinfunction "1_1") (pintype "passive"))
      (node (ref "D10A") (pin "2") (pinfunction "A_2") (pintype "passive"))
      (node (ref "D11A") (pin "2") (pinfunction "A_2") (pintype "passive"))
      (node (ref "D12A") (pin "2") (pinfunction "A_2") (pintype "passive"))
      (node (ref "D13A") (pin "2") (pinfunction "A_2") (pintype "passive"))
      (node (ref "D14A") (pin "2") (pinfunction "A_2") (pintype "passive"))
      (node (ref "L13A") (pin "1") (pinfunction "1_1") (pintype "passive"))
      (node (ref "P12A") (pin "4") (pinfunction "4_4") (pintype "passive"))
      (node (ref "Q10A") (pin "2") (pinfunction "S_2") (pintype "passive"))
      (node (ref "Q12A") (pin "2") (pinfunction "S_2") (pintype "passive"))
      (node (ref "R18A") (pin "2") (pinfunction "2_2") (pintype "passive"))
      (node (ref "R19A") (pin "2") (pinfunction "2_2") (pintype "passive"))
      (node (ref "R32A") (pin "1") (pinfunction "1_1") (pintype "passive"))
      (node (ref "R34A") (pin "1") (pinfunction "1_1") (pintype "passive"))
      (node (ref "U10A") (pin "7") (pinfunction "GND_7") (pintype "power_in"))
      (node (ref "U11A") (pin "13") (pinfunction "HPGND_13") (pintype "power_in"))
      (node (ref "U11A") (pin "18") (pinfunction "AGND_18") (pintype "power_in"))
      (node (ref "U11A") (pin "29") (pinfunction "PAD_29") (pintype "passive"))
      (node (ref "U11A") (pin "4") (pinfunction "DGND_4") (pintype "power_in"))
      (node (ref "U12A") (pin "7") (pinfunction "GND_7") (pintype "power_in"))
      (node (ref "U13A") (pin "2") (pinfunction "LR_2") (pintype "input"))
      (node (ref "U13A") (pin "5") (pinfunction "GND_5") (pintype "power_in"))
    )
    (net (code "33") (name "Net-(C30A-Pad2)") (class "Default")
      (node (ref "C30A") (pin "2") (pinfunction "2_2") (pintype "passive"))
      (node (ref "L10A") (pin "1") (pinfunction "1_1") (pintype "passive"))
    )
    (net (code "34") (name "Net-(C31A-Pad2)") (class "Default")
      (node (ref "C31A") (pin "2") (pinfunction "2_2") (pintype "passive"))
      (node (ref "L11A") (pin "1") (pinfunction "1_1") (pintype "passive"))
    )
    (net (code "35") (name "Net-(C35A-Pad2)") (class "Default")
      (node (ref "C35A") (pin "2") (pinfunction "2_2") (pintype "passive"))
      (node (ref "C36A") (pin "1") (pinfunction "1_1") (pintype "passive"))
      (node (ref "R22A") (pin "2") (pinfunction "2_2") (pintype "passive"))
      (node (ref "R23A") (pin "1") (pinfunction "1_1") (pintype "passive"))
    )
    (net (code "36") (name "Net-(Q10A-D)") (class "Default")
      (node (ref "Q10A") (pin "3") (pinfunction "D_3") (pintype "passive"))
      (node (ref "Q12A") (pin "1") (pinfunction "G_1") (pintype "passive"))
      (node (ref "R17A") (pin "2") (pinfunction "2_2") (pintype "passive"))
    )
    (net (code "37") (name "Net-(Q11A-G)") (class "Default")
      (node (ref "C32A") (pin "1") (pinfunction "1_1") (pintype "passive"))
      (node (ref "Q11A") (pin "1") (pinfunction "G_1") (pintype "passive"))
      (node (ref "R17A") (pin "1") (pinfunction "1_1") (pintype "passive"))
      (node (ref "R20A") (pin "1") (pinfunction "1_1") (pintype "passive"))
    )
    (net (code "38") (name "Net-(Q12A-D)") (class "Default")
      (node (ref "Q12A") (pin "3") (pinfunction "D_3") (pintype "passive"))
      (node (ref "R21A") (pin "2") (pinfunction "2_2") (pintype "passive"))
    )
    (net (code "39") (name "Net-(R23A-Pad2)") (class "Default")
      (node (ref "R23A") (pin "2") (pinfunction "2_2") (pintype "passive"))
      (node (ref "R24A") (pin "1") (pinfunction "1_1") (pintype "passive"))
      (node (ref "R25A") (pin "1") (pinfunction "1_1") (pintype "passive"))
      (node (ref "R28A") (pin "1") (pinfunction "1_1") (pintype "passive"))
    )
    (net (code "40") (name "Net-(U10A-+IN)") (class "Default")
      (node (ref "C19A") (pin "2") (pinfunction "2_2") (pintype "passive"))
      (node (ref "U10A") (pin "2") (pinfunction "BYP_2") (pintype "passive"))
      (node (ref "U10A") (pin "3") (pinfunction "+IN_3") (pintype "input"))
    )
    (net (code "41") (name "Net-(U10A--IN)") (class "Default")
      (node (ref "R10A") (pin "2") (pinfunction "2_2") (pintype "passive"))
      (node (ref "R12A") (pin "1") (pinfunction "1_1") (pintype "passive"))
      (node (ref "U10A") (pin "4") (pinfunction "-IN_4") (pintype "input"))
    )
    (net (code "42") (name "Net-(U11A-CE)") (class "Default")
      (node (ref "R11A") (pin "1") (pinfunction "1_1") (pintype "passive"))
      (node (ref "U11A") (pin "26") (pinfunction "CE_26") (pintype "input"))
    )
    (net (code "43") (name "Net-(U11A-DACREF)") (class "Default")
      (node (ref "C10A") (pin "2") (pinfunction "2_2") (pintype "passive"))
      (node (ref "C11A") (pin "1") (pinfunction "1_1") (pintype "passive"))
      (node (ref "U11A") (pin "25") (pinfunction "DACREF_25") (pintype "passive"))
    )
    (net (code "44") (name "Net-(U11A-LOUT2)") (class "Default")
      (node (ref "C26A") (pin "1") (pinfunction "1_1") (pintype "passive"))
      (node (ref "U11A") (pin "15") (pinfunction "LOUT2_15") (pintype "output"))
    )
    (net (code "45") (name "Net-(U11A-OUT3)") (class "Default")
      (node (ref "L12A") (pin "1") (pinfunction "1_1") (pintype "passive"))
      (node (ref "U11A") (pin "10") (pinfunction "OUT3_10") (pintype "output"))
    )
    (net (code "46") (name "Net-(U11A-ROUT2)") (class "Default")
      (node (ref "C28A") (pin "1") (pinfunction "1_1") (pintype "passive"))
      (node (ref "U11A") (pin "14") (pinfunction "ROUT2_14") (pintype "output"))
    )
    (net (code "47") (name "Net-(U12A-+IN)") (class "Default")
      (node (ref "C29A") (pin "2") (pinfunction "2_2") (pintype "passive"))
      (node (ref "U12A") (pin "2") (pinfunction "BYP_2") (pintype "passive"))
      (node (ref "U12A") (pin "3") (pinfunction "+IN_3") (pintype "input"))
    )
    (net (code "48") (name "Net-(U12A--IN)") (class "Default")
      (node (ref "R13A") (pin "2") (pinfunction "2_2") (pintype "passive"))
      (node (ref "R14A") (pin "1") (pinfunction "1_1") (pintype "passive"))
      (node (ref "U12A") (pin "4") (pinfunction "-IN_4") (pintype "input"))
    )
    (net (code "49") (name "P1.8V_VGEN3") (class "Default")
      (node (ref "R24A") (pin "2") (pinfunction "2_2") (pintype "passive"))
    )
    (net (code "50") (name "P3.3V_DELAYED") (class "Default")
      (node (ref "C32A") (pin "2") (pinfunction "2_2") (pintype "passive"))
      (node (ref "C33A") (pin "2") (pinfunction "2_2") (pintype "passive"))
      (node (ref "P12A") (pin "1") (pinfunction "1_1") (pintype "passive"))
      (node (ref "Q11A") (pin "2") (pinfunction "S_2") (pintype "passive"))
      (node (ref "R10B") (pin "2") (pinfunction "2_2") (pintype "passive"))
      (node (ref "R11B") (pin "2") (pinfunction "2_2") (pintype "passive"))
      (node (ref "R20A") (pin "2") (pinfunction "2_2") (pintype "passive"))
      (node (ref "R29A") (pin "2") (pinfunction "2_2") (pintype "passive"))
      (node (ref "R31A") (pin "2") (pinfunction "2_2") (pintype "passive"))
      (node (ref "U13A") (pin "1") (pinfunction "VDD_1") (pintype "power_in"))
    )
    (net (code "51") (name "P5.0V_DELAYED") (class "Default")
      (node (ref "C18A") (pin "2") (pinfunction "2_2") (pintype "passive"))
      (node (ref "C27A") (pin "2") (pinfunction "2_2") (pintype "passive"))
      (node (ref "U10A") (pin "6") (pinfunction "VDD_6") (pintype "power_in"))
      (node (ref "U12A") (pin "6") (pinfunction "VDD_6") (pintype "power_in"))
    )
    (net (code "52") (name "VANA") (class "Default")
      (node (ref "R28A") (pin "2") (pinfunction "2_2") (pintype "passive"))
    )
    (net (code "53") (name "unconnected-(U11A-LIN2-Pad22)") (class "Default")
      (node (ref "U11A") (pin "22") (pinfunction "LIN2_22") (pintype "input+no_connect"))
    )
    (net (code "54") (name "unconnected-(U11A-RIN2-Pad21)") (class "Default")
      (node (ref "U11A") (pin "21") (pinfunction "RIN2_21") (pintype "input+no_connect"))
    )
  )
)
